# main_board_schematic.net
KiCad netlist of a schematic drawn in EAGLE
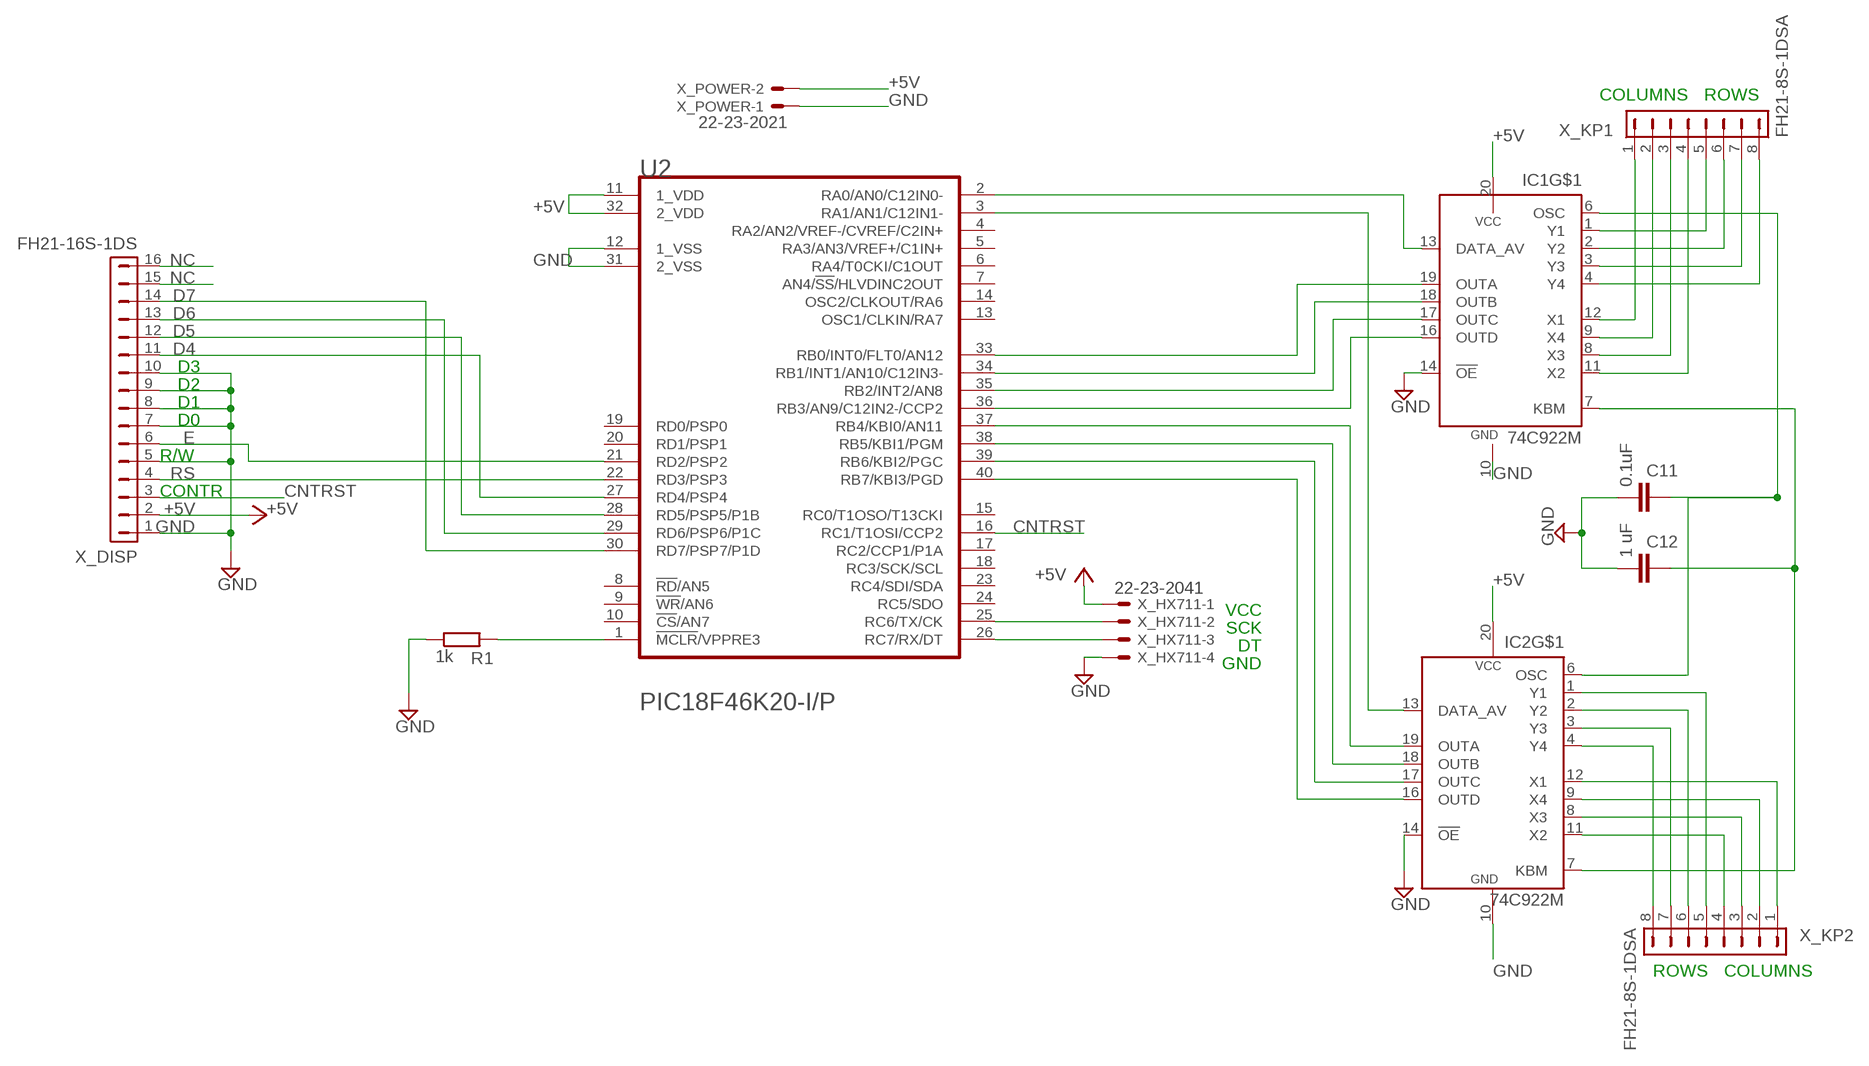
[diagram p0: schematic, sheet 1]

(export (version "E")
  (design (tool "Eeschema 10.0.6"))
  (components
    (comp (ref "C11")
      (value "0.1uF")
      (footprint "eagle-import:C2.5-2")
      (libsource (lib "eagle-import") (part "C2.5/2"))
    )
    (comp (ref "C12")
      (value "1 uF")
      (footprint "eagle-import:C2.5-2")
      (libsource (lib "eagle-import") (part "C2.5/2"))
    )
    (comp (ref "IC1")
      (value "74C922M")
      (footprint "eagle-import:SO20W")
      (libsource (lib "eagle-import") (part "74C922M"))
    )
    (comp (ref "IC2")
      (value "74C922M")
      (footprint "eagle-import:SO20W")
      (libsource (lib "eagle-import") (part "74C922M"))
    )
    (comp (ref "R1")
      (value "1k")
      (footprint "eagle-import:R0603")
      (libsource (lib "eagle-import") (part "R-EU_R0603"))
    )
    (comp (ref "U2")
      (value "MICROCHIP_PIC18F46K20-I-PMICROCHIP_PIC18F46K20-I-P_0_0")
      (footprint "eagle-import:MICROCHIP_PIC18F46K20-I-P_0")
      (fields (field (name "MF") "Microchip") (field (name "MPN") "PIC18F46K20-I/P"))
      (libsource (lib "eagle-import") (part "MICROCHIP_PIC18F46K20-I-PMICROCHIP_PIC18F46K20-I-P_0_0"))
    )
    (comp (ref "X_DISP")
      (value "FH21-16S-1DS")
      (footprint "eagle-import:FH21-16S-1DS")
      (libsource (lib "eagle-import") (part "FH21-16S-1DS"))
    )
    (comp (ref "X_HX711")
      (value "22-23-2041")
      (footprint "eagle-import:22-23-2041")
      (fields (field (name "MF") "MOLEX"))
      (libsource (lib "eagle-import") (part "22-23-2041"))
    )
    (comp (ref "X_KP1")
      (value "FH21-8S-1DSA")
      (footprint "eagle-import:FH21-8S-1DSA")
      (libsource (lib "eagle-import") (part "FH21-8S-1DSA"))
    )
    (comp (ref "X_KP2")
      (value "FH21-8S-1DSA")
      (footprint "eagle-import:FH21-8S-1DSA")
      (libsource (lib "eagle-import") (part "FH21-8S-1DSA"))
    )
    (comp (ref "X_POWER")
      (value "22-23-2021")
      (footprint "eagle-import:22-23-2021")
      (fields (field (name "MF") "MOLEX"))
      (libsource (lib "eagle-import") (part "22-23-2021"))
    )
  )
  (nets
    (net (code "1") (name "+5V") (class "Default")
      (node (ref "IC1") (pin "20") (pinfunction "VCC_20") (pintype "power_in"))
      (node (ref "IC2") (pin "20") (pinfunction "VCC_20") (pintype "power_in"))
      (node (ref "U2") (pin "11") (pinfunction "1_VDD_11") (pintype "power_in"))
      (node (ref "U2") (pin "32") (pinfunction "2_VDD_32") (pintype "power_in"))
      (node (ref "X_DISP") (pin "2") (pinfunction "2_2") (pintype "passive"))
      (node (ref "X_HX711") (pin "1") (pinfunction "S_1") (pintype "passive"))
      (node (ref "X_POWER") (pin "2") (pinfunction "S_2") (pintype "passive"))
    )
    (net (code "2") (name "/CNTRST") (class "Default")
      (node (ref "U2") (pin "16") (pinfunction "RC1/T1OSI/CCP2_16") (pintype "bidirectional"))
      (node (ref "X_DISP") (pin "3") (pinfunction "3_3") (pintype "passive"))
    )
    (net (code "3") (name "/D4") (class "Default")
      (node (ref "U2") (pin "27") (pinfunction "RD4/PSP4_27") (pintype "bidirectional"))
      (node (ref "X_DISP") (pin "11") (pinfunction "11_11") (pintype "passive"))
    )
    (net (code "4") (name "/D5") (class "Default")
      (node (ref "U2") (pin "28") (pinfunction "RD5/PSP5/P1B_28") (pintype "bidirectional"))
      (node (ref "X_DISP") (pin "12") (pinfunction "12_12") (pintype "passive"))
    )
    (net (code "5") (name "/D6") (class "Default")
      (node (ref "U2") (pin "29") (pinfunction "RD6/PSP6/P1C_29") (pintype "bidirectional"))
      (node (ref "X_DISP") (pin "13") (pinfunction "13_13") (pintype "passive"))
    )
    (net (code "6") (name "/D7") (class "Default")
      (node (ref "U2") (pin "30") (pinfunction "RD7/PSP7/P1D_30") (pintype "bidirectional"))
      (node (ref "X_DISP") (pin "14") (pinfunction "14_14") (pintype "passive"))
    )
    (net (code "7") (name "/E") (class "Default")
      (node (ref "U2") (pin "21") (pinfunction "RD2/PSP2_21") (pintype "bidirectional"))
      (node (ref "X_DISP") (pin "6") (pinfunction "6_6") (pintype "passive"))
    )
    (net (code "8") (name "/NC") (class "Default")
      (node (ref "X_DISP") (pin "15") (pinfunction "15_15") (pintype "passive"))
      (node (ref "X_DISP") (pin "16") (pinfunction "16_16") (pintype "passive"))
    )
    (net (code "9") (name "/RS") (class "Default")
      (node (ref "U2") (pin "22") (pinfunction "RD3/PSP3_22") (pintype "bidirectional"))
      (node (ref "X_DISP") (pin "4") (pinfunction "4_4") (pintype "passive"))
    )
    (net (code "10") (name "GND") (class "Default")
      (node (ref "C11") (pin "2") (pinfunction "2_2") (pintype "passive"))
      (node (ref "C12") (pin "2") (pinfunction "2_2") (pintype "passive"))
      (node (ref "IC1") (pin "10") (pinfunction "GND_10") (pintype "power_in"))
      (node (ref "IC1") (pin "14") (pinfunction "~{OE}_14") (pintype "input"))
      (node (ref "IC2") (pin "10") (pinfunction "GND_10") (pintype "power_in"))
      (node (ref "IC2") (pin "14") (pinfunction "~{OE}_14") (pintype "input"))
      (node (ref "R1") (pin "1") (pinfunction "1_1") (pintype "passive"))
      (node (ref "U2") (pin "12") (pinfunction "1_VSS_12") (pintype "power_in"))
      (node (ref "U2") (pin "31") (pinfunction "2_VSS_31") (pintype "power_in"))
      (node (ref "X_DISP") (pin "1") (pinfunction "1_1") (pintype "passive"))
      (node (ref "X_DISP") (pin "10") (pinfunction "10_10") (pintype "passive"))
      (node (ref "X_DISP") (pin "5") (pinfunction "5_5") (pintype "passive"))
      (node (ref "X_DISP") (pin "7") (pinfunction "7_7") (pintype "passive"))
      (node (ref "X_DISP") (pin "8") (pinfunction "8_8") (pintype "passive"))
      (node (ref "X_DISP") (pin "9") (pinfunction "9_9") (pintype "passive"))
      (node (ref "X_HX711") (pin "4") (pinfunction "S_4") (pintype "passive"))
      (node (ref "X_POWER") (pin "1") (pinfunction "S_1") (pintype "passive"))
    )
    (net (code "11") (name "Net-(IC1A-DATA_AV)") (class "Default")
      (node (ref "IC1") (pin "13") (pinfunction "DATA_AV_13") (pintype "output"))
      (node (ref "U2") (pin "2") (pinfunction "RA0/AN0/C12IN0-_2") (pintype "bidirectional"))
    )
    (net (code "12") (name "Net-(IC1A-KBM)") (class "Default")
      (node (ref "C12") (pin "1") (pinfunction "1_1") (pintype "passive"))
      (node (ref "IC1") (pin "7") (pinfunction "KBM_7") (pintype "input"))
      (node (ref "IC2") (pin "7") (pinfunction "KBM_7") (pintype "input"))
    )
    (net (code "13") (name "Net-(IC1A-OSC)") (class "Default")
      (node (ref "C11") (pin "1") (pinfunction "1_1") (pintype "passive"))
      (node (ref "IC1") (pin "6") (pinfunction "OSC_6") (pintype "input"))
      (node (ref "IC2") (pin "6") (pinfunction "OSC_6") (pintype "input"))
    )
    (net (code "14") (name "Net-(IC1A-OUTA)") (class "Default")
      (node (ref "IC1") (pin "19") (pinfunction "OUTA_19") (pintype "output"))
      (node (ref "U2") (pin "33") (pinfunction "RB0/INT0/FLT0/AN12_33") (pintype "bidirectional"))
    )
    (net (code "15") (name "Net-(IC1A-OUTB)") (class "Default")
      (node (ref "IC1") (pin "18") (pinfunction "OUTB_18") (pintype "output"))
      (node (ref "U2") (pin "34") (pinfunction "RB1/INT1/AN10/C12IN3-_34") (pintype "bidirectional"))
    )
    (net (code "16") (name "Net-(IC1A-OUTC)") (class "Default")
      (node (ref "IC1") (pin "17") (pinfunction "OUTC_17") (pintype "output"))
      (node (ref "U2") (pin "35") (pinfunction "RB2/INT2/AN8_35") (pintype "bidirectional"))
    )
    (net (code "17") (name "Net-(IC1A-OUTD)") (class "Default")
      (node (ref "IC1") (pin "16") (pinfunction "OUTD_16") (pintype "output"))
      (node (ref "U2") (pin "36") (pinfunction "RB3/AN9/C12IN2-/CCP2_36") (pintype "bidirectional"))
    )
    (net (code "18") (name "Net-(IC1A-X1)") (class "Default")
      (node (ref "IC1") (pin "12") (pinfunction "X1_12") (pintype "input"))
      (node (ref "X_KP1") (pin "1") (pinfunction "1_1") (pintype "passive"))
    )
    (net (code "19") (name "Net-(IC1A-X2)") (class "Default")
      (node (ref "IC1") (pin "11") (pinfunction "X2_11") (pintype "input"))
      (node (ref "X_KP1") (pin "4") (pinfunction "4_4") (pintype "passive"))
    )
    (net (code "20") (name "Net-(IC1A-X3)") (class "Default")
      (node (ref "IC1") (pin "8") (pinfunction "X3_8") (pintype "input"))
      (node (ref "X_KP1") (pin "3") (pinfunction "3_3") (pintype "passive"))
    )
    (net (code "21") (name "Net-(IC1A-X4)") (class "Default")
      (node (ref "IC1") (pin "9") (pinfunction "X4_9") (pintype "input"))
      (node (ref "X_KP1") (pin "2") (pinfunction "2_2") (pintype "passive"))
    )
    (net (code "22") (name "Net-(IC1A-Y1)") (class "Default")
      (node (ref "IC1") (pin "1") (pinfunction "Y1_1") (pintype "input"))
      (node (ref "X_KP1") (pin "5") (pinfunction "5_5") (pintype "passive"))
    )
    (net (code "23") (name "Net-(IC1A-Y2)") (class "Default")
      (node (ref "IC1") (pin "2") (pinfunction "Y2_2") (pintype "input"))
      (node (ref "X_KP1") (pin "6") (pinfunction "6_6") (pintype "passive"))
    )
    (net (code "24") (name "Net-(IC1A-Y3)") (class "Default")
      (node (ref "IC1") (pin "3") (pinfunction "Y3_3") (pintype "input"))
      (node (ref "X_KP1") (pin "7") (pinfunction "7_7") (pintype "passive"))
    )
    (net (code "25") (name "Net-(IC1A-Y4)") (class "Default")
      (node (ref "IC1") (pin "4") (pinfunction "Y4_4") (pintype "input"))
      (node (ref "X_KP1") (pin "8") (pinfunction "8_8") (pintype "passive"))
    )
    (net (code "26") (name "Net-(IC2A-DATA_AV)") (class "Default")
      (node (ref "IC2") (pin "13") (pinfunction "DATA_AV_13") (pintype "output"))
      (node (ref "U2") (pin "3") (pinfunction "RA1/AN1/C12IN1-_3") (pintype "bidirectional"))
    )
    (net (code "27") (name "Net-(IC2A-OUTA)") (class "Default")
      (node (ref "IC2") (pin "19") (pinfunction "OUTA_19") (pintype "output"))
      (node (ref "U2") (pin "37") (pinfunction "RB4/KBI0/AN11_37") (pintype "bidirectional"))
    )
    (net (code "28") (name "Net-(IC2A-OUTB)") (class "Default")
      (node (ref "IC2") (pin "18") (pinfunction "OUTB_18") (pintype "output"))
      (node (ref "U2") (pin "38") (pinfunction "RB5/KBI1/PGM_38") (pintype "bidirectional"))
    )
    (net (code "29") (name "Net-(IC2A-OUTC)") (class "Default")
      (node (ref "IC2") (pin "17") (pinfunction "OUTC_17") (pintype "output"))
      (node (ref "U2") (pin "39") (pinfunction "RB6/KBI2/PGC_39") (pintype "bidirectional"))
    )
    (net (code "30") (name "Net-(IC2A-OUTD)") (class "Default")
      (node (ref "IC2") (pin "16") (pinfunction "OUTD_16") (pintype "output"))
      (node (ref "U2") (pin "40") (pinfunction "RB7/KBI3/PGD_40") (pintype "bidirectional"))
    )
    (net (code "31") (name "Net-(IC2A-X1)") (class "Default")
      (node (ref "IC2") (pin "12") (pinfunction "X1_12") (pintype "input"))
      (node (ref "X_KP2") (pin "1") (pinfunction "1_1") (pintype "passive"))
    )
    (net (code "32") (name "Net-(IC2A-X2)") (class "Default")
      (node (ref "IC2") (pin "11") (pinfunction "X2_11") (pintype "input"))
      (node (ref "X_KP2") (pin "4") (pinfunction "4_4") (pintype "passive"))
    )
    (net (code "33") (name "Net-(IC2A-X3)") (class "Default")
      (node (ref "IC2") (pin "8") (pinfunction "X3_8") (pintype "input"))
      (node (ref "X_KP2") (pin "3") (pinfunction "3_3") (pintype "passive"))
    )
    (net (code "34") (name "Net-(IC2A-X4)") (class "Default")
      (node (ref "IC2") (pin "9") (pinfunction "X4_9") (pintype "input"))
      (node (ref "X_KP2") (pin "2") (pinfunction "2_2") (pintype "passive"))
    )
    (net (code "35") (name "Net-(IC2A-Y1)") (class "Default")
      (node (ref "IC2") (pin "1") (pinfunction "Y1_1") (pintype "input"))
      (node (ref "X_KP2") (pin "5") (pinfunction "5_5") (pintype "passive"))
    )
    (net (code "36") (name "Net-(IC2A-Y2)") (class "Default")
      (node (ref "IC2") (pin "2") (pinfunction "Y2_2") (pintype "input"))
      (node (ref "X_KP2") (pin "6") (pinfunction "6_6") (pintype "passive"))
    )
    (net (code "37") (name "Net-(IC2A-Y3)") (class "Default")
      (node (ref "IC2") (pin "3") (pinfunction "Y3_3") (pintype "input"))
      (node (ref "X_KP2") (pin "7") (pinfunction "7_7") (pintype "passive"))
    )
    (net (code "38") (name "Net-(IC2A-Y4)") (class "Default")
      (node (ref "IC2") (pin "4") (pinfunction "Y4_4") (pintype "input"))
      (node (ref "X_KP2") (pin "8") (pinfunction "8_8") (pintype "passive"))
    )
    (net (code "39") (name "Net-(U2-RC6{slash}TX{slash}CK)") (class "Default")
      (node (ref "U2") (pin "25") (pinfunction "RC6/TX/CK_25") (pintype "bidirectional"))
      (node (ref "X_HX711") (pin "2") (pinfunction "S_2") (pintype "passive"))
    )
    (net (code "40") (name "Net-(U2-RC7{slash}RX{slash}DT)") (class "Default")
      (node (ref "U2") (pin "26") (pinfunction "RC7/RX/DT_26") (pintype "bidirectional"))
      (node (ref "X_HX711") (pin "3") (pinfunction "S_3") (pintype "passive"))
    )
    (net (code "41") (name "Net-(U2-~{MCLR}{slash}VPPRE3)") (class "Default")
      (node (ref "R1") (pin "2") (pinfunction "2_2") (pintype "passive"))
      (node (ref "U2") (pin "1") (pinfunction "~{MCLR}/VPPRE3_1") (pintype "input"))
    )
    (net (code "42") (name "unconnected-(U2-AN4{slash}~{SS}{slash}HLVDINC2OUT-Pad7)") (class "Default")
      (node (ref "U2") (pin "7") (pinfunction "AN4/~{SS}/HLVDINC2OUT_7") (pintype "bidirectional"))
    )
    (net (code "43") (name "unconnected-(U2-OSC1{slash}CLKIN{slash}RA7-Pad13)") (class "Default")
      (node (ref "U2") (pin "13") (pinfunction "OSC1/CLKIN/RA7_13") (pintype "bidirectional"))
    )
    (net (code "44") (name "unconnected-(U2-OSC2{slash}CLKOUT{slash}RA6-Pad14)") (class "Default")
      (node (ref "U2") (pin "14") (pinfunction "OSC2/CLKOUT/RA6_14") (pintype "bidirectional"))
    )
    (net (code "45") (name "unconnected-(U2-RA2{slash}AN2{slash}VREF-{slash}CVREF{slash}C2IN+-Pad4)") (class "Default")
      (node (ref "U2") (pin "4") (pinfunction "RA2/AN2/VREF-/CVREF/C2IN+_4") (pintype "bidirectional"))
    )
    (net (code "46") (name "unconnected-(U2-RA3{slash}AN3{slash}VREF+{slash}C1IN+-Pad5)") (class "Default")
      (node (ref "U2") (pin "5") (pinfunction "RA3/AN3/VREF+/C1IN+_5") (pintype "bidirectional"))
    )
    (net (code "47") (name "unconnected-(U2-RA4{slash}T0CKI{slash}C1OUT-Pad6)") (class "Default")
      (node (ref "U2") (pin "6") (pinfunction "RA4/T0CKI/C1OUT_6") (pintype "bidirectional"))
    )
    (net (code "48") (name "unconnected-(U2-RC0{slash}T1OSO{slash}T13CKI-Pad15)") (class "Default")
      (node (ref "U2") (pin "15") (pinfunction "RC0/T1OSO/T13CKI_15") (pintype "bidirectional"))
    )
    (net (code "49") (name "unconnected-(U2-RC2{slash}CCP1{slash}P1A-Pad17)") (class "Default")
      (node (ref "U2") (pin "17") (pinfunction "RC2/CCP1/P1A_17") (pintype "bidirectional"))
    )
    (net (code "50") (name "unconnected-(U2-RC3{slash}SCK{slash}SCL-Pad18)") (class "Default")
      (node (ref "U2") (pin "18") (pinfunction "RC3/SCK/SCL_18") (pintype "bidirectional"))
    )
    (net (code "51") (name "unconnected-(U2-RC4{slash}SDI{slash}SDA-Pad23)") (class "Default")
      (node (ref "U2") (pin "23") (pinfunction "RC4/SDI/SDA_23") (pintype "bidirectional"))
    )
    (net (code "52") (name "unconnected-(U2-RC5{slash}SDO-Pad24)") (class "Default")
      (node (ref "U2") (pin "24") (pinfunction "RC5/SDO_24") (pintype "bidirectional"))
    )
    (net (code "53") (name "unconnected-(U2-RD0{slash}PSP0-Pad19)") (class "Default")
      (node (ref "U2") (pin "19") (pinfunction "RD0/PSP0_19") (pintype "bidirectional"))
    )
    (net (code "54") (name "unconnected-(U2-RD1{slash}PSP1-Pad20)") (class "Default")
      (node (ref "U2") (pin "20") (pinfunction "RD1/PSP1_20") (pintype "bidirectional"))
    )
    (net (code "55") (name "unconnected-(U2-~{CS}{slash}AN7-Pad10)") (class "Default")
      (node (ref "U2") (pin "10") (pinfunction "~{CS}/AN7_10") (pintype "bidirectional"))
    )
    (net (code "56") (name "unconnected-(U2-~{RD}{slash}AN5-Pad8)") (class "Default")
      (node (ref "U2") (pin "8") (pinfunction "~{RD}/AN5_8") (pintype "bidirectional"))
    )
    (net (code "57") (name "unconnected-(U2-~{WR}{slash}AN6-Pad9)") (class "Default")
      (node (ref "U2") (pin "9") (pinfunction "~{WR}/AN6_9") (pintype "bidirectional"))
    )
  )
)
